# zulu_a7_3.net
KiCad netlist of a schematic drawn in Altium Designer
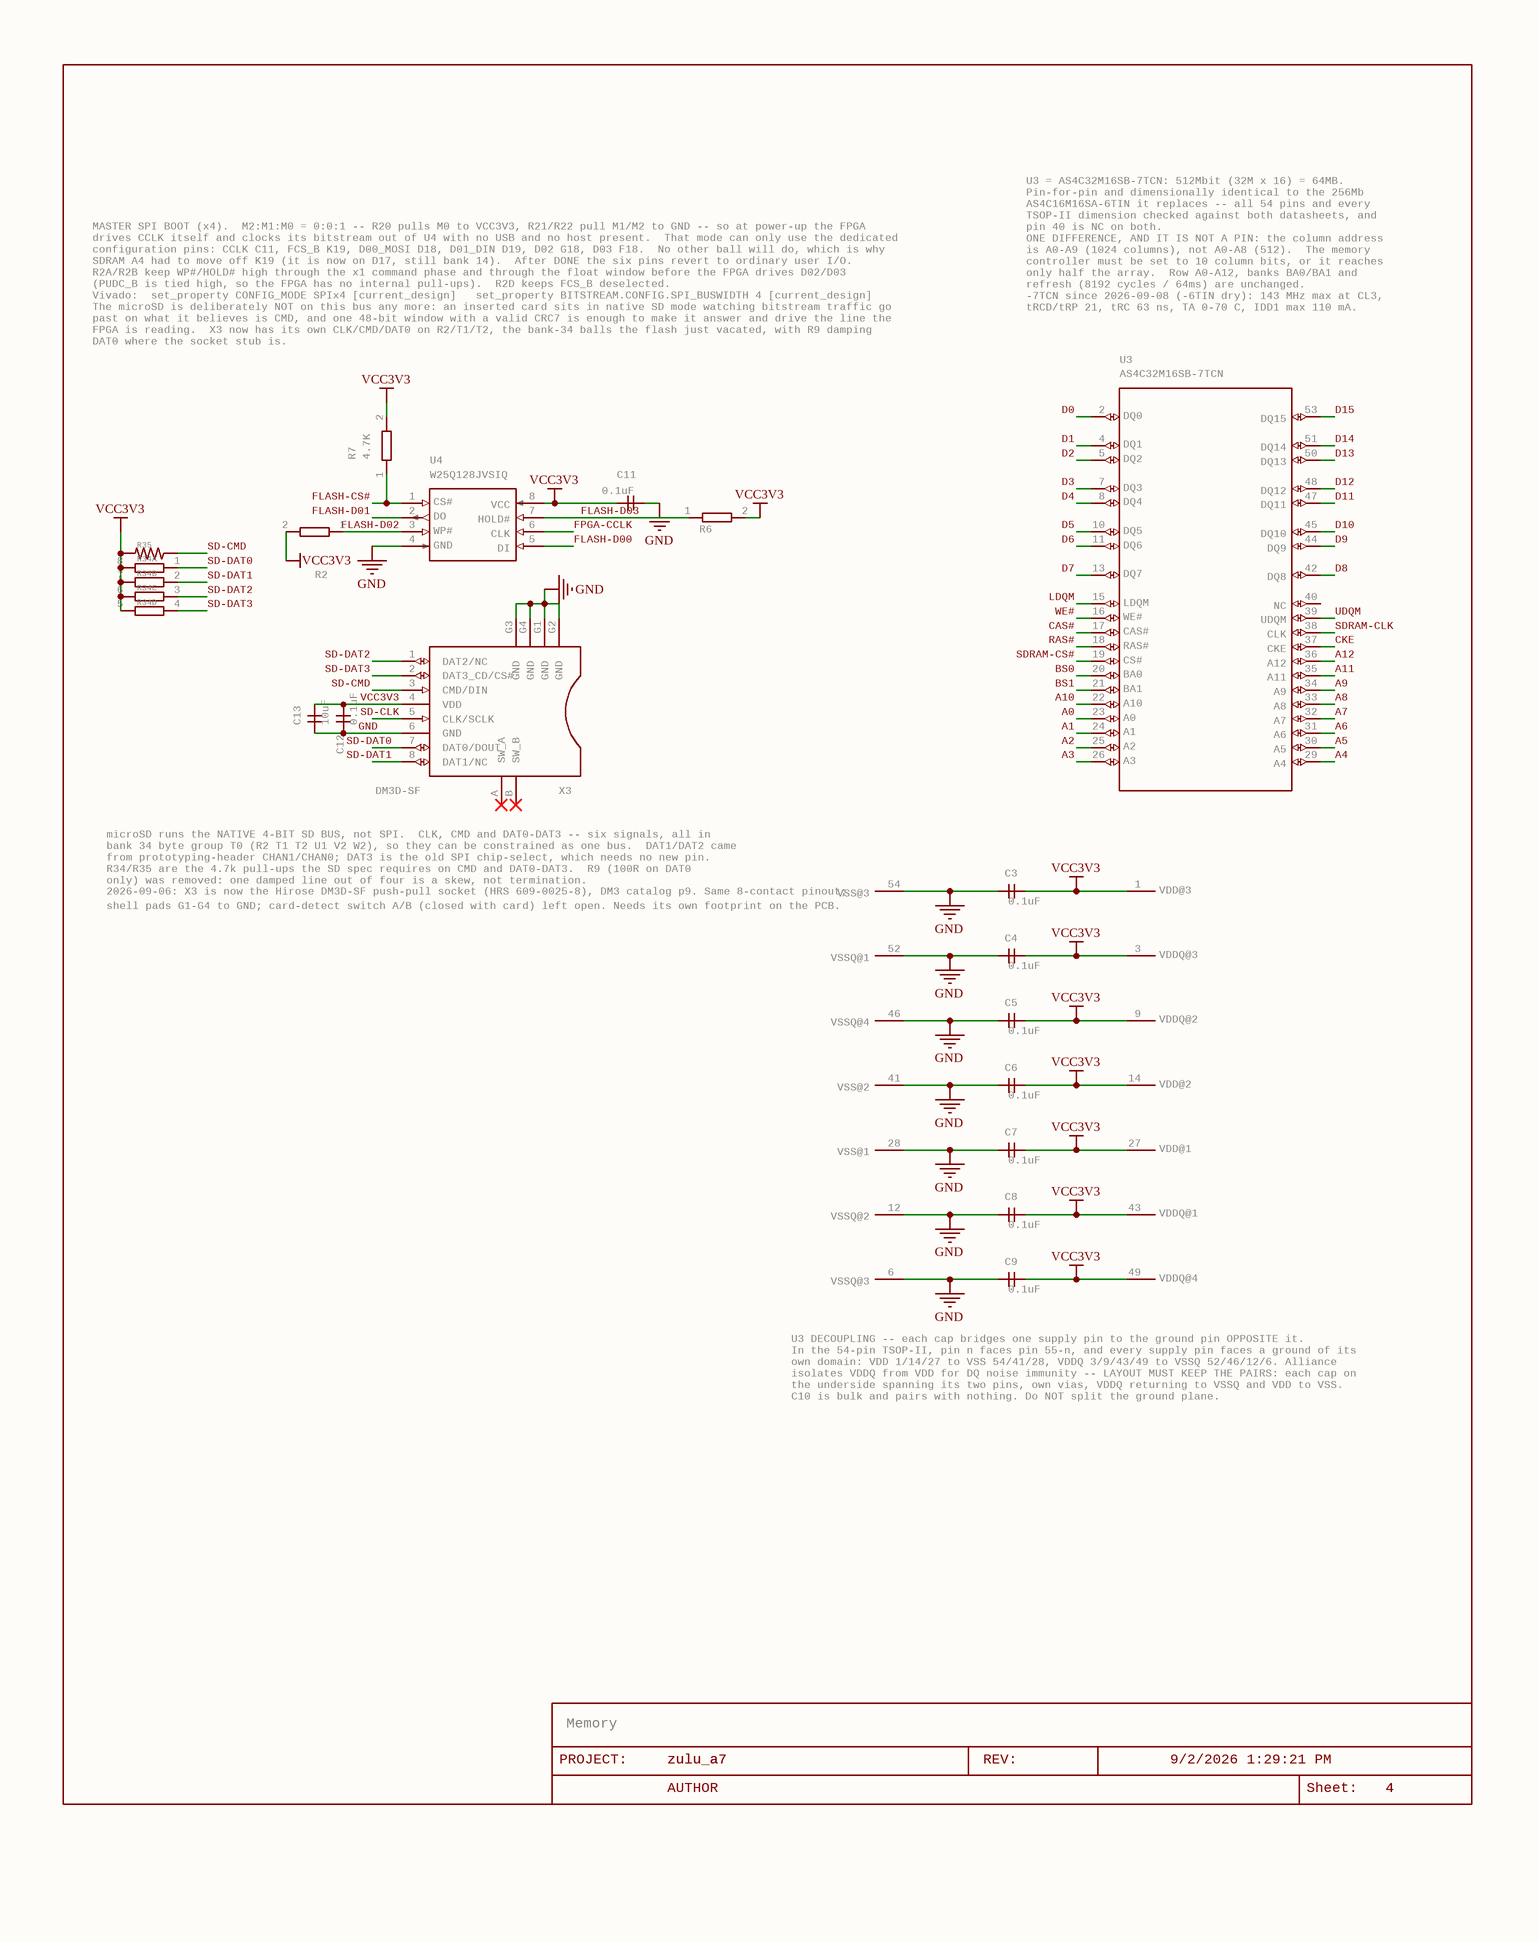
[diagram p0: zulu_a7_3.SchDoc]

(export (version "E")
  (design (tool "Eeschema 10.0.6"))
  (components
    (comp (ref "C3")
      (value "0.1uF")
      (footprint "C0402")
      (description "CAPACITOR, generic non-polarized, horizontal pins")
      (fields (field (name "MANF") "Murata"))
      (libsource (lib "") (part "C-GENERICC0402_6"))
    )
    (comp (ref "C4")
      (value "0.1uF")
      (footprint "C0402")
      (description "CAPACITOR, generic non-polarized, horizontal pins")
      (fields (field (name "MANF") "Murata"))
      (libsource (lib "") (part "C-GENERICC0402_5"))
    )
    (comp (ref "C5")
      (value "0.1uF")
      (footprint "C0402")
      (description "CAPACITOR, generic non-polarized, horizontal pins")
      (fields (field (name "MANF") "Murata"))
      (libsource (lib "") (part "C-GENERICC0402_4"))
    )
    (comp (ref "C6")
      (value "0.1uF")
      (footprint "C0402")
      (description "CAPACITOR, generic non-polarized, horizontal pins")
      (fields (field (name "MANF") "Murata"))
      (libsource (lib "rcl") (part "C-GENERICC0402"))
    )
    (comp (ref "C7")
      (value "0.1uF")
      (footprint "C0402")
      (description "CAPACITOR, generic non-polarized, horizontal pins")
      (fields (field (name "MANF") "Murata"))
      (libsource (lib "") (part "C-GENERICC0402_1"))
    )
    (comp (ref "C8")
      (value "0.1uF")
      (footprint "C0402")
      (description "CAPACITOR, generic non-polarized, horizontal pins")
      (fields (field (name "MANF") "Murata"))
      (libsource (lib "") (part "C-GENERICC0402_3"))
    )
    (comp (ref "C9")
      (value "0.1uF")
      (footprint "C0402")
      (description "CAPACITOR, generic non-polarized, horizontal pins")
      (fields (field (name "MANF") "Murata"))
      (libsource (lib "") (part "C-GENERICC0402_2"))
    )
    (comp (ref "C11")
      (value "0.1uF")
      (footprint "C0402")
      (description "CAPACITOR, generic non-polarized, horizontal pins")
      (fields (field (name "MANF") "Murata"))
      (libsource (lib "") (part "C-GENERICC0402_2"))
    )
    (comp (ref "C12")
      (value "0.1uF")
      (footprint "C0402")
      (description "CAPACITOR, generic non-polarized, horizontal pins")
      (fields (field (name "MANF") "Murata"))
      (libsource (lib "") (part "C-GENERICC0402_2"))
    )
    (comp (ref "C13")
      (value "10uF")
      (footprint "C0603")
      (description "CAPACITOR, generic non-polarized, horizontal pins")
      (fields (field (name "MANF") "Murata"))
      (libsource (lib "rcl") (part "C-GENERICC0603"))
    )
    (comp (ref "FRAME7")
      (value "DOCFIELD")
      (description "DOCUMENT FIELD")
      (fields
        (field (name "LAST_DATE_TIME") "9/2/2026 1:29:21 PM")
        (field (name "SHEET") "Sheet:")
        (field (name "SHEET_1") "4")
        (field (name "REV") "REV:")
        (field (name "PROJECT") "PROJECT:")
        (field (name "DRAWING_NAME") "zulu_a7")
        (field (name "AUTHOR") "AUTHOR")
        (field (name "DRAWING_NAME_1") "zulu_a7")
        (field (name "SHEET_2") "4")
        (field (name "LIBRARYNAME") "ctambe")
      )
      (libsource (lib "ctambe") (part "DOCFIELD"))
    )
    (comp (ref "R2")
      (value "4.7K")
      (footprint "R0201")
      (fields (field (name "MANF") "Yageo"))
      (libsource (lib "rcl") (part "R-WIDER0201"))
    )
    (comp (ref "R6")
      (value "4.7K")
      (footprint "R0201")
      (fields (field (name "MANF") "Yageo"))
      (libsource (lib "rcl") (part "R-WIDER0201"))
    )
    (comp (ref "R7")
      (value "4.7K")
      (footprint "R0201")
      (fields (field (name "MANF") "Yageo"))
      (libsource (lib "rcl") (part "R-WIDER0201"))
    )
    (comp (ref "R34")
      (value "4.7K")
      (footprint "742C083")
      (description "Resistor 4-pack   Package of four resistors.")
      (fields (field (name "MANF") "CTS") (field (name "LIBRARYNAME") "ctambe"))
      (libsource (lib "ctambe") (part "RES4742"))
    )
    (comp (ref "R35")
      (value "4.7K")
      (footprint "R0402")
      (description "RESISTOR, American symbol")
      (fields (field (name "MANF") "Yageo"))
      (libsource (lib "rcl") (part "R-US_R0402"))
    )
    (comp (ref "U3")
      (value "AS4C32M16SB-7TCN")
      (footprint "TSOPII-54")
      (fields
        (field (name "GATE") "VDD@3")
        (field (name "MANF") "Alliance Memory")
        (field (name "PART") "U3")
        (field (name "LIBRARYNAME") "ctambe")
      )
      (libsource (lib "") (part "SDRAM-X16-ALLIANCE-512M_1"))
    )
    (comp (ref "U4")
      (value "W25Q128JVSIQ")
      (footprint "SOIC-8_208MIL")
      (description "SPI Flash")
      (fields
        (field (name "PART") "U4")
        (field (name "MANF") "Winbond")
        (field (name "GATE") "DI")
        (field (name "LIBRARYNAME") "ctambe")
      )
      (libsource (lib "ctambe") (part "SPI_FLASH-SOIC_150_208"))
    )
    (comp (ref "X3")
      (value "DM3D-SF")
      (footprint "DM3D-SF")
      (description "microSD socket, push-pull, Hirose DM3D-SF")
      (fields (field (name "MANF") "Hirose") (field (name "LIBRARYNAME") "ctambe"))
      (libsource (lib "ctambe") (part "MICROSD_CONDM3D-SF"))
    )
  )
  (nets
    (net (code "1") (name "/A0") (class "Default")
      (node (ref "U3") (pin "23") (pinfunction "P$1_23") (pintype "bidirectional"))
    )
    (net (code "2") (name "/A1") (class "Default")
      (node (ref "U3") (pin "24") (pinfunction "P$1_24") (pintype "bidirectional"))
    )
    (net (code "3") (name "/A2") (class "Default")
      (node (ref "U3") (pin "25") (pinfunction "P$1_25") (pintype "bidirectional"))
    )
    (net (code "4") (name "/A3") (class "Default")
      (node (ref "U3") (pin "26") (pinfunction "P$1_26") (pintype "bidirectional"))
    )
    (net (code "5") (name "/A4") (class "Default")
      (node (ref "U3") (pin "29") (pinfunction "P$1_29") (pintype "bidirectional"))
    )
    (net (code "6") (name "/A5") (class "Default")
      (node (ref "U3") (pin "30") (pinfunction "P$1_30") (pintype "bidirectional"))
    )
    (net (code "7") (name "/A6") (class "Default")
      (node (ref "U3") (pin "31") (pinfunction "P$1_31") (pintype "bidirectional"))
    )
    (net (code "8") (name "/A7") (class "Default")
      (node (ref "U3") (pin "32") (pinfunction "P$1_32") (pintype "bidirectional"))
    )
    (net (code "9") (name "/A8") (class "Default")
      (node (ref "U3") (pin "33") (pinfunction "P$1_33") (pintype "bidirectional"))
    )
    (net (code "10") (name "/A9") (class "Default")
      (node (ref "U3") (pin "34") (pinfunction "P$1_34") (pintype "bidirectional"))
    )
    (net (code "11") (name "/A10") (class "Default")
      (node (ref "U3") (pin "22") (pinfunction "P$1_22") (pintype "bidirectional"))
    )
    (net (code "12") (name "/A11") (class "Default")
      (node (ref "U3") (pin "35") (pinfunction "P$1_35") (pintype "bidirectional"))
    )
    (net (code "13") (name "/A12") (class "Default")
      (node (ref "U3") (pin "36") (pinfunction "P$1_36") (pintype "bidirectional"))
    )
    (net (code "14") (name "/BS0") (class "Default")
      (node (ref "U3") (pin "20") (pinfunction "P$1_20") (pintype "bidirectional"))
    )
    (net (code "15") (name "/BS1") (class "Default")
      (node (ref "U3") (pin "21") (pinfunction "P$1_21") (pintype "bidirectional"))
    )
    (net (code "16") (name "/CAS#") (class "Default")
      (node (ref "U3") (pin "17") (pinfunction "P$1_17") (pintype "bidirectional"))
    )
    (net (code "17") (name "/CKE") (class "Default")
      (node (ref "U3") (pin "37") (pinfunction "P$1_37") (pintype "bidirectional"))
    )
    (net (code "18") (name "/D0") (class "Default")
      (node (ref "U3") (pin "2") (pinfunction "P$1_2") (pintype "bidirectional"))
    )
    (net (code "19") (name "/D1") (class "Default")
      (node (ref "U3") (pin "4") (pinfunction "P$1_4") (pintype "bidirectional"))
    )
    (net (code "20") (name "/D2") (class "Default")
      (node (ref "U3") (pin "5") (pinfunction "P$1_5") (pintype "bidirectional"))
    )
    (net (code "21") (name "/D3") (class "Default")
      (node (ref "U3") (pin "7") (pinfunction "P$1_7") (pintype "bidirectional"))
    )
    (net (code "22") (name "/D4") (class "Default")
      (node (ref "U3") (pin "8") (pinfunction "P$1_8") (pintype "bidirectional"))
    )
    (net (code "23") (name "/D5") (class "Default")
      (node (ref "U3") (pin "10") (pinfunction "P$1_10") (pintype "bidirectional"))
    )
    (net (code "24") (name "/D6") (class "Default")
      (node (ref "U3") (pin "11") (pinfunction "P$1_11") (pintype "bidirectional"))
    )
    (net (code "25") (name "/D7") (class "Default")
      (node (ref "U3") (pin "13") (pinfunction "P$1_13") (pintype "bidirectional"))
    )
    (net (code "26") (name "/D8") (class "Default")
      (node (ref "U3") (pin "42") (pinfunction "P$1_42") (pintype "bidirectional"))
    )
    (net (code "27") (name "/D9") (class "Default")
      (node (ref "U3") (pin "44") (pinfunction "P$1_44") (pintype "bidirectional"))
    )
    (net (code "28") (name "/D10") (class "Default")
      (node (ref "U3") (pin "45") (pinfunction "P$1_45") (pintype "bidirectional"))
    )
    (net (code "29") (name "/D11") (class "Default")
      (node (ref "U3") (pin "47") (pinfunction "P$1_47") (pintype "bidirectional"))
    )
    (net (code "30") (name "/D12") (class "Default")
      (node (ref "U3") (pin "48") (pinfunction "P$1_48") (pintype "bidirectional"))
    )
    (net (code "31") (name "/D13") (class "Default")
      (node (ref "U3") (pin "50") (pinfunction "P$1_50") (pintype "bidirectional"))
    )
    (net (code "32") (name "/D14") (class "Default")
      (node (ref "U3") (pin "51") (pinfunction "P$1_51") (pintype "bidirectional"))
    )
    (net (code "33") (name "/D15") (class "Default")
      (node (ref "U3") (pin "53") (pinfunction "P$1_53") (pintype "bidirectional"))
    )
    (net (code "34") (name "/FLASH-CS#") (class "Default")
      (node (ref "R7") (pin "1") (pinfunction "1_1") (pintype "passive"))
      (node (ref "U4") (pin "1") (pinfunction "1_1") (pintype "input"))
    )
    (net (code "35") (name "/FLASH-D00") (class "Default")
      (node (ref "U4") (pin "5") (pinfunction "1_5") (pintype "input"))
    )
    (net (code "36") (name "/FLASH-D01") (class "Default")
      (node (ref "U4") (pin "2") (pinfunction "1_2") (pintype "output"))
    )
    (net (code "37") (name "/FLASH-D02") (class "Default")
      (node (ref "R2") (pin "1") (pinfunction "1_1") (pintype "passive"))
      (node (ref "U4") (pin "3") (pinfunction "1_3") (pintype "input"))
    )
    (net (code "38") (name "/FLASH-D03") (class "Default")
      (node (ref "R6") (pin "1") (pinfunction "1_1") (pintype "passive"))
      (node (ref "U4") (pin "7") (pinfunction "1_7") (pintype "input"))
    )
    (net (code "39") (name "/FPGA-CCLK") (class "Default")
      (node (ref "U4") (pin "6") (pinfunction "1_6") (pintype "input"))
    )
    (net (code "40") (name "/LDQM") (class "Default")
      (node (ref "U3") (pin "15") (pinfunction "P$1_15") (pintype "bidirectional"))
    )
    (net (code "41") (name "/RAS#") (class "Default")
      (node (ref "U3") (pin "18") (pinfunction "P$1_18") (pintype "bidirectional"))
    )
    (net (code "42") (name "/SD-CLK") (class "Default")
      (node (ref "X3") (pin "5") (pinfunction "CLK/SCLK_5") (pintype "input"))
    )
    (net (code "43") (name "/SD-CMD") (class "Default")
      (node (ref "R35") (pin "1") (pinfunction "1_1") (pintype "passive"))
      (node (ref "X3") (pin "3") (pinfunction "CMD/DIN_3") (pintype "input"))
    )
    (net (code "44") (name "/SD-DAT0") (class "Default")
      (node (ref "R34") (pin "1") (pinfunction "1_1") (pintype "passive"))
      (node (ref "X3") (pin "7") (pinfunction "DAT0/DOUT_7") (pintype "bidirectional"))
    )
    (net (code "45") (name "/SD-DAT1") (class "Default")
      (node (ref "R34") (pin "2") (pinfunction "1_2") (pintype "passive"))
      (node (ref "X3") (pin "8") (pinfunction "DAT1/NC_8") (pintype "bidirectional"))
    )
    (net (code "46") (name "/SD-DAT2") (class "Default")
      (node (ref "R34") (pin "3") (pinfunction "1_3") (pintype "passive"))
      (node (ref "X3") (pin "1") (pinfunction "DAT2/NC_1") (pintype "bidirectional"))
    )
    (net (code "47") (name "/SD-DAT3") (class "Default")
      (node (ref "R34") (pin "4") (pinfunction "1_4") (pintype "passive"))
      (node (ref "X3") (pin "2") (pinfunction "DAT3_CD/CS#_2") (pintype "bidirectional"))
    )
    (net (code "48") (name "/SDRAM-CLK") (class "Default")
      (node (ref "U3") (pin "38") (pinfunction "P$1_38") (pintype "bidirectional"))
    )
    (net (code "49") (name "/SDRAM-CS#") (class "Default")
      (node (ref "U3") (pin "19") (pinfunction "P$1_19") (pintype "bidirectional"))
    )
    (net (code "50") (name "/UDQM") (class "Default")
      (node (ref "U3") (pin "39") (pinfunction "P$1_39") (pintype "bidirectional"))
    )
    (net (code "51") (name "/WE#") (class "Default")
      (node (ref "U3") (pin "16") (pinfunction "P$1_16") (pintype "bidirectional"))
    )
    (net (code "52") (name "GND") (class "Default")
      (node (ref "C11") (pin "1") (pinfunction "1_1") (pintype "passive"))
      (node (ref "C12") (pin "1") (pinfunction "1_1") (pintype "passive"))
      (node (ref "C13") (pin "1") (pinfunction "1_1") (pintype "passive"))
      (node (ref "C3") (pin "1") (pinfunction "1_1") (pintype "passive"))
      (node (ref "C4") (pin "1") (pinfunction "1_1") (pintype "passive"))
      (node (ref "C5") (pin "1") (pinfunction "1_1") (pintype "passive"))
      (node (ref "C6") (pin "1") (pinfunction "1_1") (pintype "passive"))
      (node (ref "C7") (pin "1") (pinfunction "1_1") (pintype "passive"))
      (node (ref "C8") (pin "1") (pinfunction "1_1") (pintype "passive"))
      (node (ref "C9") (pin "1") (pinfunction "1_1") (pintype "passive"))
      (node (ref "U3") (pin "12") (pinfunction "P$1_12") (pintype "power_in"))
      (node (ref "U3") (pin "28") (pinfunction "P$1_28") (pintype "power_in"))
      (node (ref "U3") (pin "41") (pinfunction "P$1_41") (pintype "power_in"))
      (node (ref "U3") (pin "46") (pinfunction "P$1_46") (pintype "power_in"))
      (node (ref "U3") (pin "52") (pinfunction "P$1_52") (pintype "power_in"))
      (node (ref "U3") (pin "54") (pinfunction "P$1_54") (pintype "power_in"))
      (node (ref "U3") (pin "6") (pinfunction "P$1_6") (pintype "power_in"))
      (node (ref "U4") (pin "4") (pinfunction "1_4") (pintype "input"))
      (node (ref "X3") (pin "6") (pinfunction "GND_6") (pintype "passive"))
      (node (ref "X3") (pin "G1") (pinfunction "GND_G1") (pintype "passive"))
      (node (ref "X3") (pin "G2") (pinfunction "GND_G2") (pintype "passive"))
      (node (ref "X3") (pin "G3") (pinfunction "GND_G3") (pintype "passive"))
      (node (ref "X3") (pin "G4") (pinfunction "GND_G4") (pintype "passive"))
    )
    (net (code "53") (name "VCC3V3") (class "Default")
      (node (ref "C11") (pin "2") (pinfunction "2_2") (pintype "passive"))
      (node (ref "C12") (pin "2") (pinfunction "2_2") (pintype "passive"))
      (node (ref "C13") (pin "2") (pinfunction "2_2") (pintype "passive"))
      (node (ref "C3") (pin "2") (pinfunction "2_2") (pintype "passive"))
      (node (ref "C4") (pin "2") (pinfunction "2_2") (pintype "passive"))
      (node (ref "C5") (pin "2") (pinfunction "2_2") (pintype "passive"))
      (node (ref "C6") (pin "2") (pinfunction "2_2") (pintype "passive"))
      (node (ref "C7") (pin "2") (pinfunction "2_2") (pintype "passive"))
      (node (ref "C8") (pin "2") (pinfunction "2_2") (pintype "passive"))
      (node (ref "C9") (pin "2") (pinfunction "2_2") (pintype "passive"))
      (node (ref "R2") (pin "2") (pinfunction "2_2") (pintype "passive"))
      (node (ref "R34") (pin "5") (pinfunction "2_5") (pintype "passive"))
      (node (ref "R34") (pin "6") (pinfunction "2_6") (pintype "passive"))
      (node (ref "R34") (pin "7") (pinfunction "2_7") (pintype "passive"))
      (node (ref "R34") (pin "8") (pinfunction "2_8") (pintype "passive"))
      (node (ref "R35") (pin "2") (pinfunction "2_2") (pintype "passive"))
      (node (ref "R6") (pin "2") (pinfunction "2_2") (pintype "passive"))
      (node (ref "R7") (pin "2") (pinfunction "2_2") (pintype "passive"))
      (node (ref "U3") (pin "1") (pinfunction "P$1_1") (pintype "power_in"))
      (node (ref "U3") (pin "14") (pinfunction "P$1_14") (pintype "power_in"))
      (node (ref "U3") (pin "27") (pinfunction "P$1_27") (pintype "power_in"))
      (node (ref "U3") (pin "3") (pinfunction "P$1_3") (pintype "power_in"))
      (node (ref "U3") (pin "43") (pinfunction "P$1_43") (pintype "power_in"))
      (node (ref "U3") (pin "49") (pinfunction "P$1_49") (pintype "power_in"))
      (node (ref "U3") (pin "9") (pinfunction "P$1_9") (pintype "power_in"))
      (node (ref "U4") (pin "8") (pinfunction "1_8") (pintype "input"))
      (node (ref "X3") (pin "4") (pinfunction "VDD_4") (pintype "passive"))
    )
    (net (code "54") (name "unconnected-(U3AO-P$1-Pad40)") (class "Default")
      (node (ref "U3") (pin "40") (pinfunction "P$1_40") (pintype "bidirectional"))
    )
    (net (code "55") (name "unconnected-(X3-SW_A-PadA)") (class "Default")
      (node (ref "X3") (pin "A") (pinfunction "SW_A_A") (pintype "passive+no_connect"))
    )
    (net (code "56") (name "unconnected-(X3-SW_B-PadB)") (class "Default")
      (node (ref "X3") (pin "B") (pinfunction "SW_B_B") (pintype "passive+no_connect"))
    )
  )
)
